# pcb-breakout-mdbt40.net
KiCad netlist of a schematic drawn in EAGLE
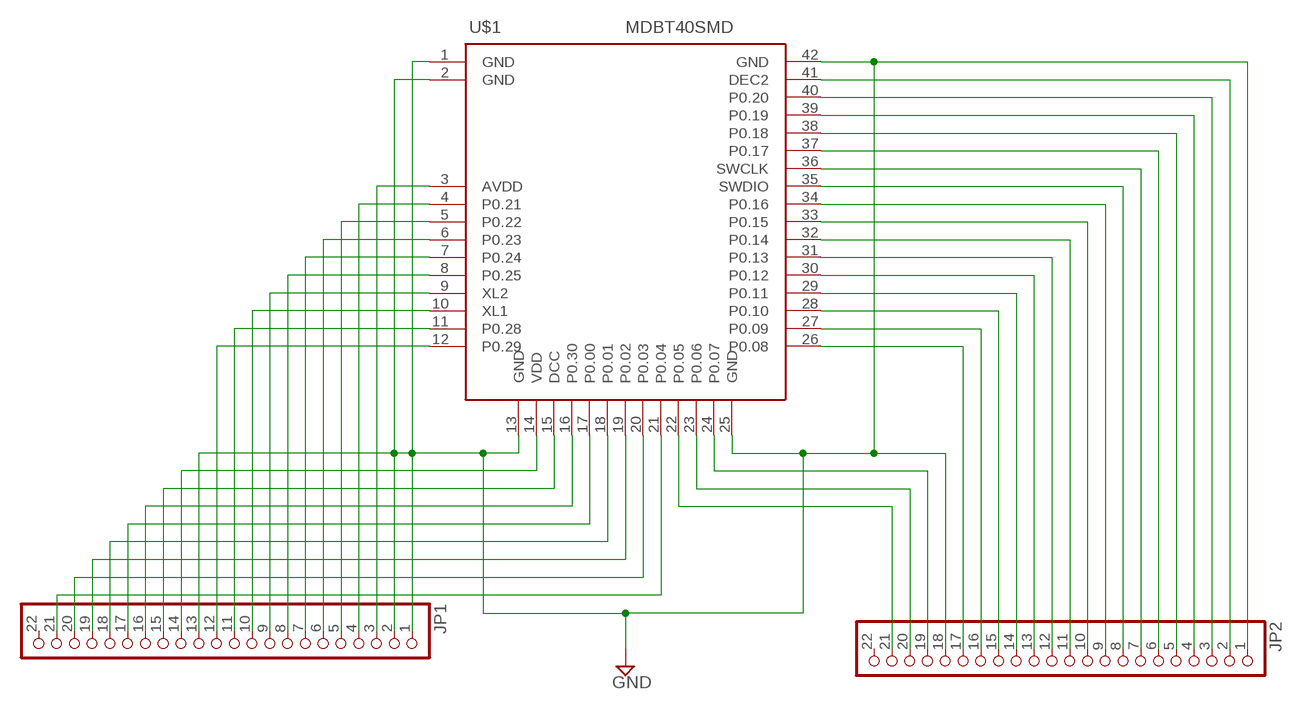
[diagram p0: schematic, sheet 1]

(export (version "E")
  (design (tool "Eeschema 10.0.6"))
  (components
    (comp (ref "JP1")
      (value "PINHD-1X22")
      (footprint "eagle-import:1X22")
      (libsource (lib "eagle-import") (part "PINHD-1X22"))
    )
    (comp (ref "JP2")
      (value "PINHD-1X22")
      (footprint "eagle-import:1X22")
      (libsource (lib "eagle-import") (part "PINHD-1X22"))
    )
    (comp (ref "U$1")
      (value "MDBT40SMD")
      (footprint "eagle-import:MDBT40")
      (libsource (lib "eagle-import") (part "MDBT40SMD"))
    )
  )
  (nets
    (net (code "1") (name "GND") (class "Default")
      (node (ref "JP1") (pin "1") (pinfunction "1_1") (pintype "passive"))
      (node (ref "JP1") (pin "13") (pinfunction "13_13") (pintype "passive"))
      (node (ref "JP1") (pin "2") (pinfunction "2_2") (pintype "passive"))
      (node (ref "JP2") (pin "1") (pinfunction "1_1") (pintype "passive"))
      (node (ref "JP2") (pin "18") (pinfunction "18_18") (pintype "passive"))
      (node (ref "U$1") (pin "1") (pinfunction "GND_1") (pintype "bidirectional"))
      (node (ref "U$1") (pin "13") (pinfunction "GND_13") (pintype "bidirectional"))
      (node (ref "U$1") (pin "2") (pinfunction "GND_2") (pintype "bidirectional"))
      (node (ref "U$1") (pin "25") (pinfunction "GND_25") (pintype "bidirectional"))
      (node (ref "U$1") (pin "42") (pinfunction "GND_42") (pintype "bidirectional"))
    )
    (net (code "2") (name "Net-(U$1-AVDD)") (class "Default")
      (node (ref "JP1") (pin "3") (pinfunction "3_3") (pintype "passive"))
      (node (ref "U$1") (pin "3") (pinfunction "AVDD_3") (pintype "bidirectional"))
    )
    (net (code "3") (name "Net-(U$1-DCC)") (class "Default")
      (node (ref "JP1") (pin "15") (pinfunction "15_15") (pintype "passive"))
      (node (ref "U$1") (pin "15") (pinfunction "DCC_15") (pintype "bidirectional"))
    )
    (net (code "4") (name "Net-(U$1-DEC2)") (class "Default")
      (node (ref "JP2") (pin "2") (pinfunction "2_2") (pintype "passive"))
      (node (ref "U$1") (pin "41") (pinfunction "DEC2_41") (pintype "bidirectional"))
    )
    (net (code "5") (name "Net-(U$1-P0.00)") (class "Default")
      (node (ref "JP1") (pin "17") (pinfunction "17_17") (pintype "passive"))
      (node (ref "U$1") (pin "17") (pinfunction "P0.00_17") (pintype "bidirectional"))
    )
    (net (code "6") (name "Net-(U$1-P0.01)") (class "Default")
      (node (ref "JP1") (pin "18") (pinfunction "18_18") (pintype "passive"))
      (node (ref "U$1") (pin "18") (pinfunction "P0.01_18") (pintype "bidirectional"))
    )
    (net (code "7") (name "Net-(U$1-P0.02)") (class "Default")
      (node (ref "JP1") (pin "19") (pinfunction "19_19") (pintype "passive"))
      (node (ref "U$1") (pin "19") (pinfunction "P0.02_19") (pintype "bidirectional"))
    )
    (net (code "8") (name "Net-(U$1-P0.03)") (class "Default")
      (node (ref "JP1") (pin "20") (pinfunction "20_20") (pintype "passive"))
      (node (ref "U$1") (pin "20") (pinfunction "P0.03_20") (pintype "bidirectional"))
    )
    (net (code "9") (name "Net-(U$1-P0.04)") (class "Default")
      (node (ref "JP1") (pin "21") (pinfunction "21_21") (pintype "passive"))
      (node (ref "U$1") (pin "21") (pinfunction "P0.04_21") (pintype "bidirectional"))
    )
    (net (code "10") (name "Net-(U$1-P0.05)") (class "Default")
      (node (ref "JP2") (pin "21") (pinfunction "21_21") (pintype "passive"))
      (node (ref "U$1") (pin "22") (pinfunction "P0.05_22") (pintype "bidirectional"))
    )
    (net (code "11") (name "Net-(U$1-P0.06)") (class "Default")
      (node (ref "JP2") (pin "20") (pinfunction "20_20") (pintype "passive"))
      (node (ref "U$1") (pin "23") (pinfunction "P0.06_23") (pintype "bidirectional"))
    )
    (net (code "12") (name "Net-(U$1-P0.07)") (class "Default")
      (node (ref "JP2") (pin "19") (pinfunction "19_19") (pintype "passive"))
      (node (ref "U$1") (pin "24") (pinfunction "P0.07_24") (pintype "bidirectional"))
    )
    (net (code "13") (name "Net-(U$1-P0.08)") (class "Default")
      (node (ref "JP2") (pin "17") (pinfunction "17_17") (pintype "passive"))
      (node (ref "U$1") (pin "26") (pinfunction "P0.08_26") (pintype "bidirectional"))
    )
    (net (code "14") (name "Net-(U$1-P0.09)") (class "Default")
      (node (ref "JP2") (pin "16") (pinfunction "16_16") (pintype "passive"))
      (node (ref "U$1") (pin "27") (pinfunction "P0.09_27") (pintype "bidirectional"))
    )
    (net (code "15") (name "Net-(U$1-P0.10)") (class "Default")
      (node (ref "JP2") (pin "15") (pinfunction "15_15") (pintype "passive"))
      (node (ref "U$1") (pin "28") (pinfunction "P0.10_28") (pintype "bidirectional"))
    )
    (net (code "16") (name "Net-(U$1-P0.11)") (class "Default")
      (node (ref "JP2") (pin "14") (pinfunction "14_14") (pintype "passive"))
      (node (ref "U$1") (pin "29") (pinfunction "P0.11_29") (pintype "bidirectional"))
    )
    (net (code "17") (name "Net-(U$1-P0.12)") (class "Default")
      (node (ref "JP2") (pin "13") (pinfunction "13_13") (pintype "passive"))
      (node (ref "U$1") (pin "30") (pinfunction "P0.12_30") (pintype "bidirectional"))
    )
    (net (code "18") (name "Net-(U$1-P0.13)") (class "Default")
      (node (ref "JP2") (pin "12") (pinfunction "12_12") (pintype "passive"))
      (node (ref "U$1") (pin "31") (pinfunction "P0.13_31") (pintype "bidirectional"))
    )
    (net (code "19") (name "Net-(U$1-P0.14)") (class "Default")
      (node (ref "JP2") (pin "11") (pinfunction "11_11") (pintype "passive"))
      (node (ref "U$1") (pin "32") (pinfunction "P0.14_32") (pintype "bidirectional"))
    )
    (net (code "20") (name "Net-(U$1-P0.15)") (class "Default")
      (node (ref "JP2") (pin "10") (pinfunction "10_10") (pintype "passive"))
      (node (ref "U$1") (pin "33") (pinfunction "P0.15_33") (pintype "bidirectional"))
    )
    (net (code "21") (name "Net-(U$1-P0.16)") (class "Default")
      (node (ref "JP2") (pin "9") (pinfunction "9_9") (pintype "passive"))
      (node (ref "U$1") (pin "34") (pinfunction "P0.16_34") (pintype "bidirectional"))
    )
    (net (code "22") (name "Net-(U$1-P0.17)") (class "Default")
      (node (ref "JP2") (pin "6") (pinfunction "6_6") (pintype "passive"))
      (node (ref "U$1") (pin "37") (pinfunction "P0.17_37") (pintype "bidirectional"))
    )
    (net (code "23") (name "Net-(U$1-P0.18)") (class "Default")
      (node (ref "JP2") (pin "5") (pinfunction "5_5") (pintype "passive"))
      (node (ref "U$1") (pin "38") (pinfunction "P0.18_38") (pintype "bidirectional"))
    )
    (net (code "24") (name "Net-(U$1-P0.19)") (class "Default")
      (node (ref "JP2") (pin "4") (pinfunction "4_4") (pintype "passive"))
      (node (ref "U$1") (pin "39") (pinfunction "P0.19_39") (pintype "bidirectional"))
    )
    (net (code "25") (name "Net-(U$1-P0.20)") (class "Default")
      (node (ref "JP2") (pin "3") (pinfunction "3_3") (pintype "passive"))
      (node (ref "U$1") (pin "40") (pinfunction "P0.20_40") (pintype "bidirectional"))
    )
    (net (code "26") (name "Net-(U$1-P0.21)") (class "Default")
      (node (ref "JP1") (pin "4") (pinfunction "4_4") (pintype "passive"))
      (node (ref "U$1") (pin "4") (pinfunction "P0.21_4") (pintype "bidirectional"))
    )
    (net (code "27") (name "Net-(U$1-P0.22)") (class "Default")
      (node (ref "JP1") (pin "5") (pinfunction "5_5") (pintype "passive"))
      (node (ref "U$1") (pin "5") (pinfunction "P0.22_5") (pintype "bidirectional"))
    )
    (net (code "28") (name "Net-(U$1-P0.23)") (class "Default")
      (node (ref "JP1") (pin "6") (pinfunction "6_6") (pintype "passive"))
      (node (ref "U$1") (pin "6") (pinfunction "P0.23_6") (pintype "bidirectional"))
    )
    (net (code "29") (name "Net-(U$1-P0.24)") (class "Default")
      (node (ref "JP1") (pin "7") (pinfunction "7_7") (pintype "passive"))
      (node (ref "U$1") (pin "7") (pinfunction "P0.24_7") (pintype "bidirectional"))
    )
    (net (code "30") (name "Net-(U$1-P0.25)") (class "Default")
      (node (ref "JP1") (pin "8") (pinfunction "8_8") (pintype "passive"))
      (node (ref "U$1") (pin "8") (pinfunction "P0.25_8") (pintype "bidirectional"))
    )
    (net (code "31") (name "Net-(U$1-P0.28)") (class "Default")
      (node (ref "JP1") (pin "11") (pinfunction "11_11") (pintype "passive"))
      (node (ref "U$1") (pin "11") (pinfunction "P0.28_11") (pintype "bidirectional"))
    )
    (net (code "32") (name "Net-(U$1-P0.29)") (class "Default")
      (node (ref "JP1") (pin "12") (pinfunction "12_12") (pintype "passive"))
      (node (ref "U$1") (pin "12") (pinfunction "P0.29_12") (pintype "bidirectional"))
    )
    (net (code "33") (name "Net-(U$1-P0.30)") (class "Default")
      (node (ref "JP1") (pin "16") (pinfunction "16_16") (pintype "passive"))
      (node (ref "U$1") (pin "16") (pinfunction "P0.30_16") (pintype "bidirectional"))
    )
    (net (code "34") (name "Net-(U$1-SWCLK)") (class "Default")
      (node (ref "JP2") (pin "7") (pinfunction "7_7") (pintype "passive"))
      (node (ref "U$1") (pin "36") (pinfunction "SWCLK_36") (pintype "bidirectional"))
    )
    (net (code "35") (name "Net-(U$1-SWDIO)") (class "Default")
      (node (ref "JP2") (pin "8") (pinfunction "8_8") (pintype "passive"))
      (node (ref "U$1") (pin "35") (pinfunction "SWDIO_35") (pintype "bidirectional"))
    )
    (net (code "36") (name "Net-(U$1-VDD)") (class "Default")
      (node (ref "JP1") (pin "14") (pinfunction "14_14") (pintype "passive"))
      (node (ref "U$1") (pin "14") (pinfunction "VDD_14") (pintype "bidirectional"))
    )
    (net (code "37") (name "Net-(U$1-XL1)") (class "Default")
      (node (ref "JP1") (pin "10") (pinfunction "10_10") (pintype "passive"))
      (node (ref "U$1") (pin "10") (pinfunction "XL1_10") (pintype "bidirectional"))
    )
    (net (code "38") (name "Net-(U$1-XL2)") (class "Default")
      (node (ref "JP1") (pin "9") (pinfunction "9_9") (pintype "passive"))
      (node (ref "U$1") (pin "9") (pinfunction "XL2_9") (pintype "bidirectional"))
    )
    (net (code "39") (name "unconnected-(JP1-Pad22)") (class "Default")
      (node (ref "JP1") (pin "22") (pinfunction "22_22") (pintype "passive"))
    )
    (net (code "40") (name "unconnected-(JP2-Pad22)") (class "Default")
      (node (ref "JP2") (pin "22") (pinfunction "22_22") (pintype "passive"))
    )
  )
)
